# M_H_ext_disp.net
KiCad netlist of a schematic drawn in EAGLE
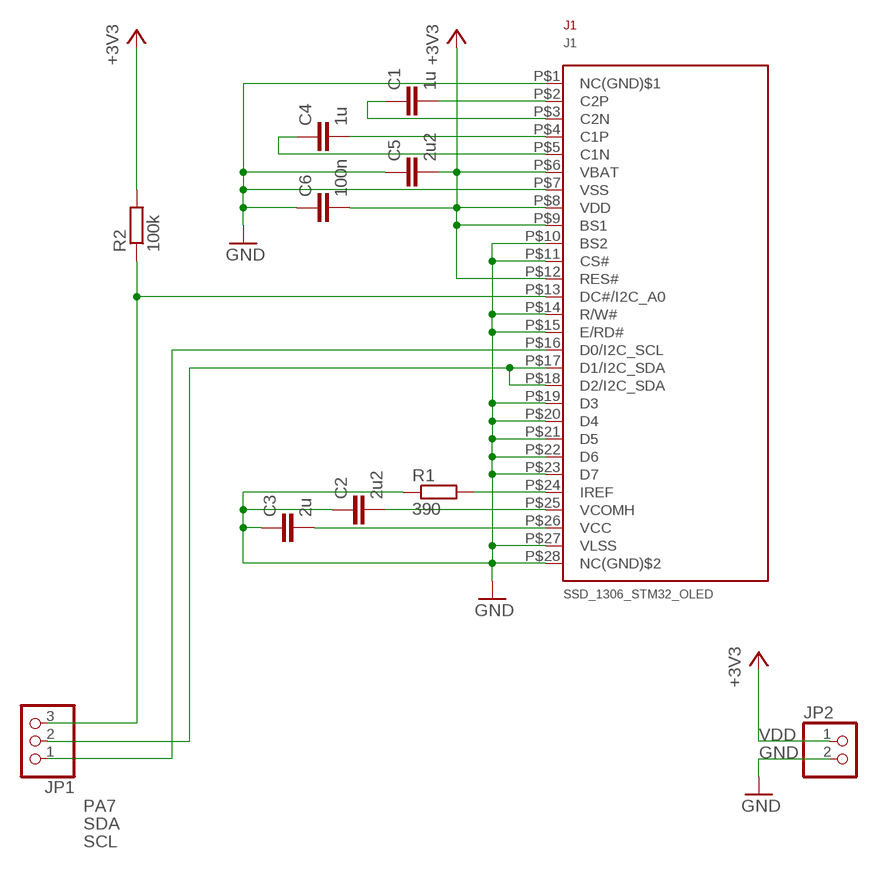
[diagram p0: schematic, sheet 1]

(export (version "E")
  (design (tool "Eeschema 10.0.6"))
  (components
    (comp (ref "C1")
      (value "1u")
      (footprint "eagle-import:C0603")
      (libsource (lib "eagle-import") (part "C-EUC0603"))
    )
    (comp (ref "C2")
      (value "2u2")
      (footprint "eagle-import:C0603")
      (libsource (lib "eagle-import") (part "C-EUC0603"))
    )
    (comp (ref "C3")
      (value "2u")
      (footprint "eagle-import:C0603")
      (libsource (lib "eagle-import") (part "C-EUC0603"))
    )
    (comp (ref "C4")
      (value "1u")
      (footprint "eagle-import:C0603")
      (libsource (lib "eagle-import") (part "C-EUC0603"))
    )
    (comp (ref "C5")
      (value "2u2")
      (footprint "eagle-import:C0603")
      (libsource (lib "eagle-import") (part "C-EUC0603"))
    )
    (comp (ref "C6")
      (value "100n")
      (footprint "eagle-import:C0603")
      (libsource (lib "eagle-import") (part "C-EUC0603"))
    )
    (comp (ref "J1")
      (value "SSD_1306_STM32_OLED")
      (footprint "eagle-import:SSD_1306_STM32_OLED")
      (libsource (lib "eagle-import") (part "SSD_1306_STM32_OLED"))
    )
    (comp (ref "JP1")
      (value "PINHD-1X3")
      (footprint "eagle-import:1X03")
      (libsource (lib "eagle-import") (part "PINHD-1X3"))
    )
    (comp (ref "JP2")
      (value "PINHD-1X2")
      (footprint "eagle-import:1X02")
      (libsource (lib "eagle-import") (part "PINHD-1X2"))
    )
    (comp (ref "R1")
      (value "390")
      (footprint "eagle-import:R0603")
      (libsource (lib "eagle-import") (part "R-EU_R0603"))
    )
    (comp (ref "R2")
      (value "100k")
      (footprint "eagle-import:R0603")
      (libsource (lib "eagle-import") (part "R-EU_R0603"))
    )
  )
  (nets
    (net (code "1") (name "+3V3") (class "Default")
      (node (ref "C5") (pin "2") (pinfunction "2_2") (pintype "passive"))
      (node (ref "C6") (pin "2") (pinfunction "2_2") (pintype "passive"))
      (node (ref "J1") (pin "P$12") (pinfunction "RES#_P$12") (pintype "input"))
      (node (ref "J1") (pin "P$6") (pinfunction "VBAT_P$6") (pintype "input"))
      (node (ref "J1") (pin "P$8") (pinfunction "VDD_P$8") (pintype "power_in"))
      (node (ref "J1") (pin "P$9") (pinfunction "BS1_P$9") (pintype "input"))
      (node (ref "JP2") (pin "1") (pinfunction "1_1") (pintype "passive"))
      (node (ref "R2") (pin "2") (pinfunction "2_2") (pintype "passive"))
    )
    (net (code "2") (name "/PA7") (class "Default")
      (node (ref "J1") (pin "P$13") (pinfunction "DC#/I2C_A0_P$13") (pintype "input"))
      (node (ref "JP1") (pin "3") (pinfunction "3_3") (pintype "passive"))
      (node (ref "R2") (pin "1") (pinfunction "1_1") (pintype "passive"))
    )
    (net (code "3") (name "/SCL") (class "Default")
      (node (ref "J1") (pin "P$16") (pinfunction "D0/I2C_SCL_P$16") (pintype "bidirectional"))
      (node (ref "JP1") (pin "1") (pinfunction "1_1") (pintype "passive"))
    )
    (net (code "4") (name "/SDA") (class "Default")
      (node (ref "J1") (pin "P$17") (pinfunction "D1/I2C_SDA_P$17") (pintype "bidirectional"))
      (node (ref "J1") (pin "P$18") (pinfunction "D2/I2C_SDA_P$18") (pintype "bidirectional"))
      (node (ref "JP1") (pin "2") (pinfunction "2_2") (pintype "passive"))
    )
    (net (code "5") (name "GND") (class "Default")
      (node (ref "C2") (pin "1") (pinfunction "1_1") (pintype "passive"))
      (node (ref "C3") (pin "1") (pinfunction "1_1") (pintype "passive"))
      (node (ref "C5") (pin "1") (pinfunction "1_1") (pintype "passive"))
      (node (ref "C6") (pin "1") (pinfunction "1_1") (pintype "passive"))
      (node (ref "J1") (pin "P$1") (pinfunction "NC(GND)$1_P$1") (pintype "input"))
      (node (ref "J1") (pin "P$10") (pinfunction "BS2_P$10") (pintype "input"))
      (node (ref "J1") (pin "P$11") (pinfunction "CS#_P$11") (pintype "input"))
      (node (ref "J1") (pin "P$14") (pinfunction "R/W#_P$14") (pintype "input"))
      (node (ref "J1") (pin "P$15") (pinfunction "E/RD#_P$15") (pintype "input"))
      (node (ref "J1") (pin "P$19") (pinfunction "D3_P$19") (pintype "bidirectional"))
      (node (ref "J1") (pin "P$20") (pinfunction "D4_P$20") (pintype "bidirectional"))
      (node (ref "J1") (pin "P$21") (pinfunction "D5_P$21") (pintype "bidirectional"))
      (node (ref "J1") (pin "P$22") (pinfunction "D6_P$22") (pintype "bidirectional"))
      (node (ref "J1") (pin "P$23") (pinfunction "D7_P$23") (pintype "bidirectional"))
      (node (ref "J1") (pin "P$27") (pinfunction "VLSS_P$27") (pintype "power_in"))
      (node (ref "J1") (pin "P$28") (pinfunction "NC(GND)$2_P$28") (pintype "input"))
      (node (ref "J1") (pin "P$7") (pinfunction "VSS_P$7") (pintype "power_in"))
      (node (ref "JP2") (pin "2") (pinfunction "2_2") (pintype "passive"))
      (node (ref "R1") (pin "1") (pinfunction "1_1") (pintype "passive"))
    )
    (net (code "6") (name "Net-(J1-C1N)") (class "Default")
      (node (ref "C4") (pin "1") (pinfunction "1_1") (pintype "passive"))
      (node (ref "J1") (pin "P$5") (pinfunction "C1N_P$5") (pintype "input"))
    )
    (net (code "7") (name "Net-(J1-C1P)") (class "Default")
      (node (ref "C4") (pin "2") (pinfunction "2_2") (pintype "passive"))
      (node (ref "J1") (pin "P$4") (pinfunction "C1P_P$4") (pintype "input"))
    )
    (net (code "8") (name "Net-(J1-C2N)") (class "Default")
      (node (ref "C1") (pin "1") (pinfunction "1_1") (pintype "passive"))
      (node (ref "J1") (pin "P$3") (pinfunction "C2N_P$3") (pintype "input"))
    )
    (net (code "9") (name "Net-(J1-C2P)") (class "Default")
      (node (ref "C1") (pin "2") (pinfunction "2_2") (pintype "passive"))
      (node (ref "J1") (pin "P$2") (pinfunction "C2P_P$2") (pintype "input"))
    )
    (net (code "10") (name "Net-(J1-IREF)") (class "Default")
      (node (ref "J1") (pin "P$24") (pinfunction "IREF_P$24") (pintype "input"))
      (node (ref "R1") (pin "2") (pinfunction "2_2") (pintype "passive"))
    )
    (net (code "11") (name "Net-(J1-VCC)") (class "Default")
      (node (ref "C3") (pin "2") (pinfunction "2_2") (pintype "passive"))
      (node (ref "J1") (pin "P$26") (pinfunction "VCC_P$26") (pintype "power_in"))
    )
    (net (code "12") (name "Net-(J1-VCOMH)") (class "Default")
      (node (ref "C2") (pin "2") (pinfunction "2_2") (pintype "passive"))
      (node (ref "J1") (pin "P$25") (pinfunction "VCOMH_P$25") (pintype "output"))
    )
  )
)
